# RS485.net
KiCad netlist of a schematic drawn in Altium Designer
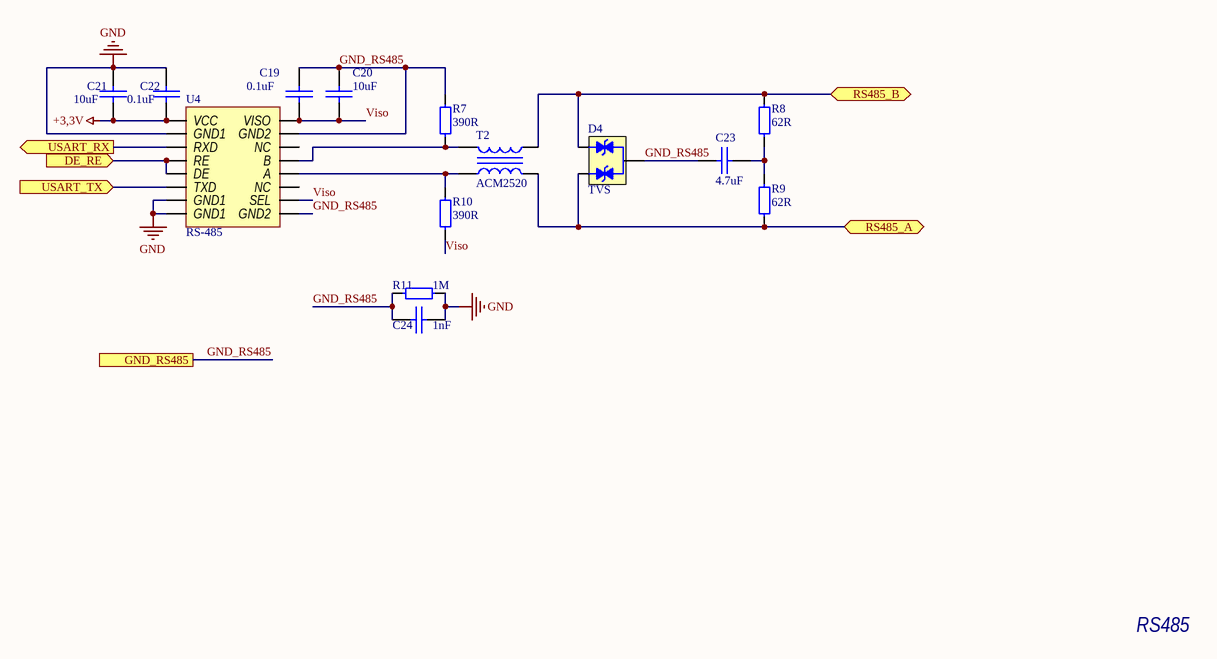
[diagram p0: RS485.SchDoc]

(export (version "E")
  (design (tool "Eeschema 10.0.6"))
  (components
    (comp (ref "C19")
      (value "0.1uF")
      (footprint "0603 Capicator")
      (description "0.1uF X7R 16V 10% 0603")
      (fields
        (field (name "MANUFACTURER") "Murata Manufacturing")
        (field (name "PART NUMBER") "GRM188R71C104KA01D")
      )
      (libsource (lib "БУС") (part "Cap 0.1uF (0603)"))
    )
    (comp (ref "C20")
      (value "10uF")
      (footprint "0603 Capicator")
      (description "10uF X5R 25V 20% 0603")
      (fields
        (field (name "MANUFACTURER") "Murata Manufacturing")
        (field (name "PART NUMBER") "GRM188R61E106M")
      )
      (libsource (lib "БУС") (part "Cap 10uF (0603)"))
    )
    (comp (ref "C21")
      (value "10uF")
      (footprint "0603 Capicator")
      (description "10uF X5R 25V 20% 0603")
      (fields
        (field (name "MANUFACTURER") "Murata Manufacturing")
        (field (name "PART NUMBER") "GRM188R61E106M")
      )
      (libsource (lib "БУС") (part "Cap 10uF (0603)"))
    )
    (comp (ref "C22")
      (value "0.1uF")
      (footprint "0603 Capicator")
      (description "0.1uF X7R 16V 10% 0603")
      (fields
        (field (name "MANUFACTURER") "Murata Manufacturing")
        (field (name "PART NUMBER") "GRM188R71C104KA01D")
      )
      (libsource (lib "БУС") (part "Cap 0.1uF (0603)"))
    )
    (comp (ref "C23")
      (value "4.7uF")
      (footprint "0603 Capicator")
      (description "4.7uF X5R 25V 10% 0603")
      (fields
        (field (name "MANUFACTURER") "Murata Manufacturing")
        (field (name "PART NUMBER") "GRM188R61E475KE11D")
      )
      (libsource (lib "БУНЭ") (part "Cap 4.7uF (0603)"))
    )
    (comp (ref "C24")
      (value "1nF")
      (footprint "0603 Capicator")
      (description "X7R 1nF 100V 10% 0603")
      (fields
        (field (name "MANUFACTURER") "Murata Manufacturing")
        (field (name "PART NUMBER") "GRM188R72A102KA01D")
      )
      (libsource (lib "БУС") (part "Cap 1nF (0603)"))
    )
    (comp (ref "D4")
      (value "TVS")
      (footprint "SOT-23")
      (fields (field (name "PART NUMBER") "SM24CANB-02HTG") (field (name "MANUFACTURER") "Littelfuse"))
      (libsource (lib "BRT_Components") (part "TVS Diode Arrays"))
    )
    (comp (ref "R7")
      (value "390R")
      (footprint "1206 RESISTOR")
      (description "0.25W 1206 390R")
      (fields (field (name "PART NUMBER") "RC1206JR-07390KL") (field (name "MANUFACTURER") "Taiwan"))
      (libsource (lib "БУС") (part "Res 390R (1206)"))
    )
    (comp (ref "R8")
      (value "62R")
      (footprint "0603 Resistor")
      (description "0.1W 0603 62R, 1%")
      (fields (field (name "PART NUMBER") "RC0603FR-0762RL") (field (name "MANUFACTURER") "Taiwan"))
      (libsource (lib "БУНЭ") (part "Res 62R (0603)"))
    )
    (comp (ref "R9")
      (value "62R")
      (footprint "0603 Resistor")
      (description "0.1W 0603 62R, 1%")
      (fields (field (name "PART NUMBER") "RC0603FR-0762RL") (field (name "MANUFACTURER") "Taiwan"))
      (libsource (lib "БУНЭ") (part "Res 62R (0603)"))
    )
    (comp (ref "R10")
      (value "390R")
      (footprint "1206 RESISTOR")
      (description "0.25W 1206 390R")
      (fields (field (name "PART NUMBER") "RC1206JR-07390KL") (field (name "MANUFACTURER") "Taiwan"))
      (libsource (lib "БУС") (part "Res 390R (1206)"))
    )
    (comp (ref "R11")
      (value "1M")
      (footprint "0603 Resistor")
      (description "0.1W 0603 1M, 1%")
      (fields (field (name "PART NUMBER") "RC0603FR-071ML") (field (name "MANUFACTURER") "Taiwan"))
      (libsource (lib "БУС") (part "Res 1M (0603)"))
    )
    (comp (ref "T2")
      (value "ACM2520")
      (footprint "ACM2520")
      (description "Common mode filters\r\nAutomotive signal line (for power train/safety)")
      (fields (field (name "MANUFACTURER") "TDK") (field (name "PART NUMBER") "ACM2520-301-2P-T002"))
      (libsource (lib "БУНЭ") (part "ACM2520"))
    )
    (comp (ref "U4")
      (value "RS-485")
      (footprint "SOIC16W")
      (description "Isolated RS-485 Half-Duplex tranciever")
      (fields (field (name "MANUFACTURER") "Mornsun") (field (name "PART NUMBER") "TDA51S485HC"))
      (libsource (lib "БУС") (part "TDA51S485HC"))
    )
  )
  (nets
    (net (code "1") (name "+3,3V") (class "Default")
      (node (ref "C21") (pin "2") (pinfunction "2_2") (pintype "passive"))
      (node (ref "C22") (pin "1") (pinfunction "1_1") (pintype "passive"))
      (node (ref "U4") (pin "1") (pinfunction "VCC_1") (pintype "passive"))
    )
    (net (code "2") (name "/DE_RE") (class "Default")
      (node (ref "U4") (pin "4") (pinfunction "RE_4") (pintype "passive"))
      (node (ref "U4") (pin "5") (pinfunction "DE_5") (pintype "passive"))
    )
    (net (code "3") (name "/GND_RS485") (class "Default")
      (node (ref "C19") (pin "2") (pinfunction "2_2") (pintype "passive"))
      (node (ref "C20") (pin "2") (pinfunction "2_2") (pintype "passive"))
      (node (ref "C23") (pin "2") (pinfunction "2_2") (pintype "passive"))
      (node (ref "C24") (pin "1") (pinfunction "1_1") (pintype "passive"))
      (node (ref "D4") (pin "3") (pinfunction "3_3") (pintype "passive"))
      (node (ref "R11") (pin "1") (pinfunction "1_1") (pintype "passive"))
      (node (ref "R7") (pin "2") (pinfunction "2_2") (pintype "passive"))
      (node (ref "U4") (pin "15") (pinfunction "GND2_15") (pintype "passive"))
      (node (ref "U4") (pin "9") (pinfunction "GND2_9") (pintype "passive"))
    )
    (net (code "4") (name "/RS485_A") (class "Default")
      (node (ref "D4") (pin "2") (pinfunction "2_2") (pintype "passive"))
      (node (ref "R9") (pin "1") (pinfunction "1_1") (pintype "passive"))
      (node (ref "T2") (pin "4") (pinfunction "4_4") (pintype "passive"))
    )
    (net (code "5") (name "/RS485_B") (class "Default")
      (node (ref "D4") (pin "1") (pinfunction "1_1") (pintype "passive"))
      (node (ref "R8") (pin "2") (pinfunction "2_2") (pintype "passive"))
      (node (ref "T2") (pin "2") (pinfunction "2_2") (pintype "passive"))
    )
    (net (code "6") (name "/USART_RX") (class "Default")
      (node (ref "U4") (pin "3") (pinfunction "RXD_3") (pintype "passive"))
    )
    (net (code "7") (name "/USART_TX") (class "Default")
      (node (ref "U4") (pin "6") (pinfunction "TXD_6") (pintype "passive"))
    )
    (net (code "8") (name "/Viso") (class "Default")
      (node (ref "C19") (pin "1") (pinfunction "1_1") (pintype "passive"))
      (node (ref "C20") (pin "1") (pinfunction "1_1") (pintype "passive"))
      (node (ref "R10") (pin "1") (pinfunction "1_1") (pintype "passive"))
      (node (ref "U4") (pin "10") (pinfunction "SEL_10") (pintype "passive"))
      (node (ref "U4") (pin "16") (pinfunction "VISO_16") (pintype "passive"))
    )
    (net (code "9") (name "GND") (class "Default")
      (node (ref "C21") (pin "1") (pinfunction "1_1") (pintype "passive"))
      (node (ref "C22") (pin "2") (pinfunction "2_2") (pintype "passive"))
      (node (ref "C24") (pin "2") (pinfunction "2_2") (pintype "passive"))
      (node (ref "R11") (pin "2") (pinfunction "2_2") (pintype "passive"))
      (node (ref "U4") (pin "2") (pinfunction "GND1_2") (pintype "passive"))
      (node (ref "U4") (pin "7") (pinfunction "GND1_7") (pintype "passive"))
      (node (ref "U4") (pin "8") (pinfunction "GND1_8") (pintype "passive"))
    )
    (net (code "10") (name "Net-(C23-Pad1)") (class "Default")
      (node (ref "C23") (pin "1") (pinfunction "1_1") (pintype "passive"))
      (node (ref "R8") (pin "1") (pinfunction "1_1") (pintype "passive"))
      (node (ref "R9") (pin "2") (pinfunction "2_2") (pintype "passive"))
    )
    (net (code "11") (name "Net-(U4-A)") (class "Default")
      (node (ref "R10") (pin "2") (pinfunction "2_2") (pintype "passive"))
      (node (ref "T2") (pin "3") (pinfunction "3_3") (pintype "passive"))
      (node (ref "U4") (pin "12") (pinfunction "A_12") (pintype "passive"))
    )
    (net (code "12") (name "Net-(U4-B)") (class "Default")
      (node (ref "R7") (pin "1") (pinfunction "1_1") (pintype "passive"))
      (node (ref "T2") (pin "1") (pinfunction "1_1") (pintype "passive"))
      (node (ref "U4") (pin "13") (pinfunction "B_13") (pintype "passive"))
    )
    (net (code "13") (name "unconnected-(U4-NC-Pad11)") (class "Default")
      (node (ref "U4") (pin "11") (pinfunction "NC_11") (pintype "passive"))
    )
    (net (code "14") (name "unconnected-(U4-NC-Pad14)") (class "Default")
      (node (ref "U4") (pin "14") (pinfunction "NC_14") (pintype "passive"))
    )
  )
)
